# Converter_3V3.net
KiCad netlist of a schematic drawn in Altium Designer
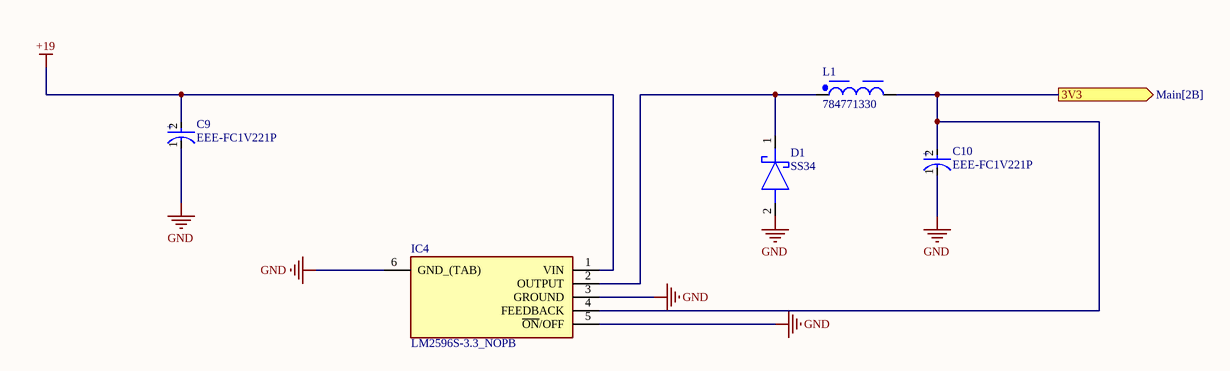
[diagram p0: Converter_3V3.SchDoc]

(export (version "E")
  (design (tool "Eeschema 10.0.6"))
  (components
    (comp (ref "C9")
      (value "EEE-FC1V221P")
      (footprint "FP-FC-G-MFG")
      (description "CAP ALUM 220UF 20% 35V SMD")
      (fields (field (name "TOLERANCE") "20%") (field (name "VOLTAGE") "35V"))
      (libsource (lib "Altium Content Vault") (part "8eef7423fb450d55d321f8a63fae760"))
    )
    (comp (ref "C10")
      (value "EEE-FC1V221P")
      (footprint "FP-FC-G-MFG")
      (description "CAP ALUM 220UF 20% 35V SMD")
      (fields (field (name "TOLERANCE") "20%") (field (name "VOLTAGE") "35V"))
      (libsource (lib "Altium Content Vault") (part "8eef7423fb450d55d321f8a63fae760"))
    )
    (comp (ref "D1")
      (value "SS34")
      (footprint "SamacSys:DIOM8059X256N")
      (description "Schottky Diode")
      (fields (field (name "MOUSER PART NUMBER") "512-SS34"))
      (libsource (lib "*") (part "SS34"))
    )
    (comp (ref "IC4")
      (value "LM2596S-3.3_NOPB")
      (footprint "SamacSys:TO170P1435X465-6N")
      (description "Integrated Circuit")
      (fields
        (field (name "MANUFACTURER_PART_NUMBER") "LM2596S-3.3/NOPB")
        (field (name "MOUSER PART NUMBER") "926-LM2596S-3.3/NOPB")
      )
      (libsource (lib "*") (part "LM2596S-3.3_NOPB"))
    )
    (comp (ref "L1")
      (value "784771330")
      (footprint "WE-PDA_1260")
      (description "784771330 Power Inductor, 33Uh, Shielded, 2.8A Rohs Compliant: Yes")
      (libsource (lib "Altium Content Vault") (part "Inductor - 2"))
    )
  )
  (nets
    (net (code "1") (name "+19") (class "Default")
      (node (ref "C9") (pin "2") (pinfunction "A_2") (pintype "passive"))
      (node (ref "IC4") (pin "1") (pinfunction "VIN_1") (pintype "passive"))
    )
    (net (code "2") (name "/3V3") (class "Default")
      (node (ref "C10") (pin "2") (pinfunction "A_2") (pintype "passive"))
      (node (ref "IC4") (pin "4") (pinfunction "FEEDBACK_4") (pintype "passive"))
      (node (ref "L1") (pin "2") (pinfunction "2_2") (pintype "passive"))
    )
    (net (code "3") (name "GND") (class "Default")
      (node (ref "C10") (pin "1") (pinfunction "C_1") (pintype "passive"))
      (node (ref "C9") (pin "1") (pinfunction "C_1") (pintype "passive"))
      (node (ref "D1") (pin "2") (pinfunction "A_2") (pintype "passive"))
      (node (ref "IC4") (pin "3") (pinfunction "GROUND_3") (pintype "passive"))
      (node (ref "IC4") (pin "5") (pinfunction "~{ON}/OFF_5") (pintype "passive"))
      (node (ref "IC4") (pin "6") (pinfunction "GND_(TAB)_6") (pintype "power_in"))
    )
    (net (code "4") (name "Net-(D1-K)") (class "Default")
      (node (ref "D1") (pin "1") (pinfunction "K_1") (pintype "passive"))
      (node (ref "IC4") (pin "2") (pinfunction "OUTPUT_2") (pintype "passive"))
      (node (ref "L1") (pin "1") (pinfunction "1_1") (pintype "passive"))
    )
  )
)
